# lpf.net
KiCad netlist of a schematic drawn in Altium Designer
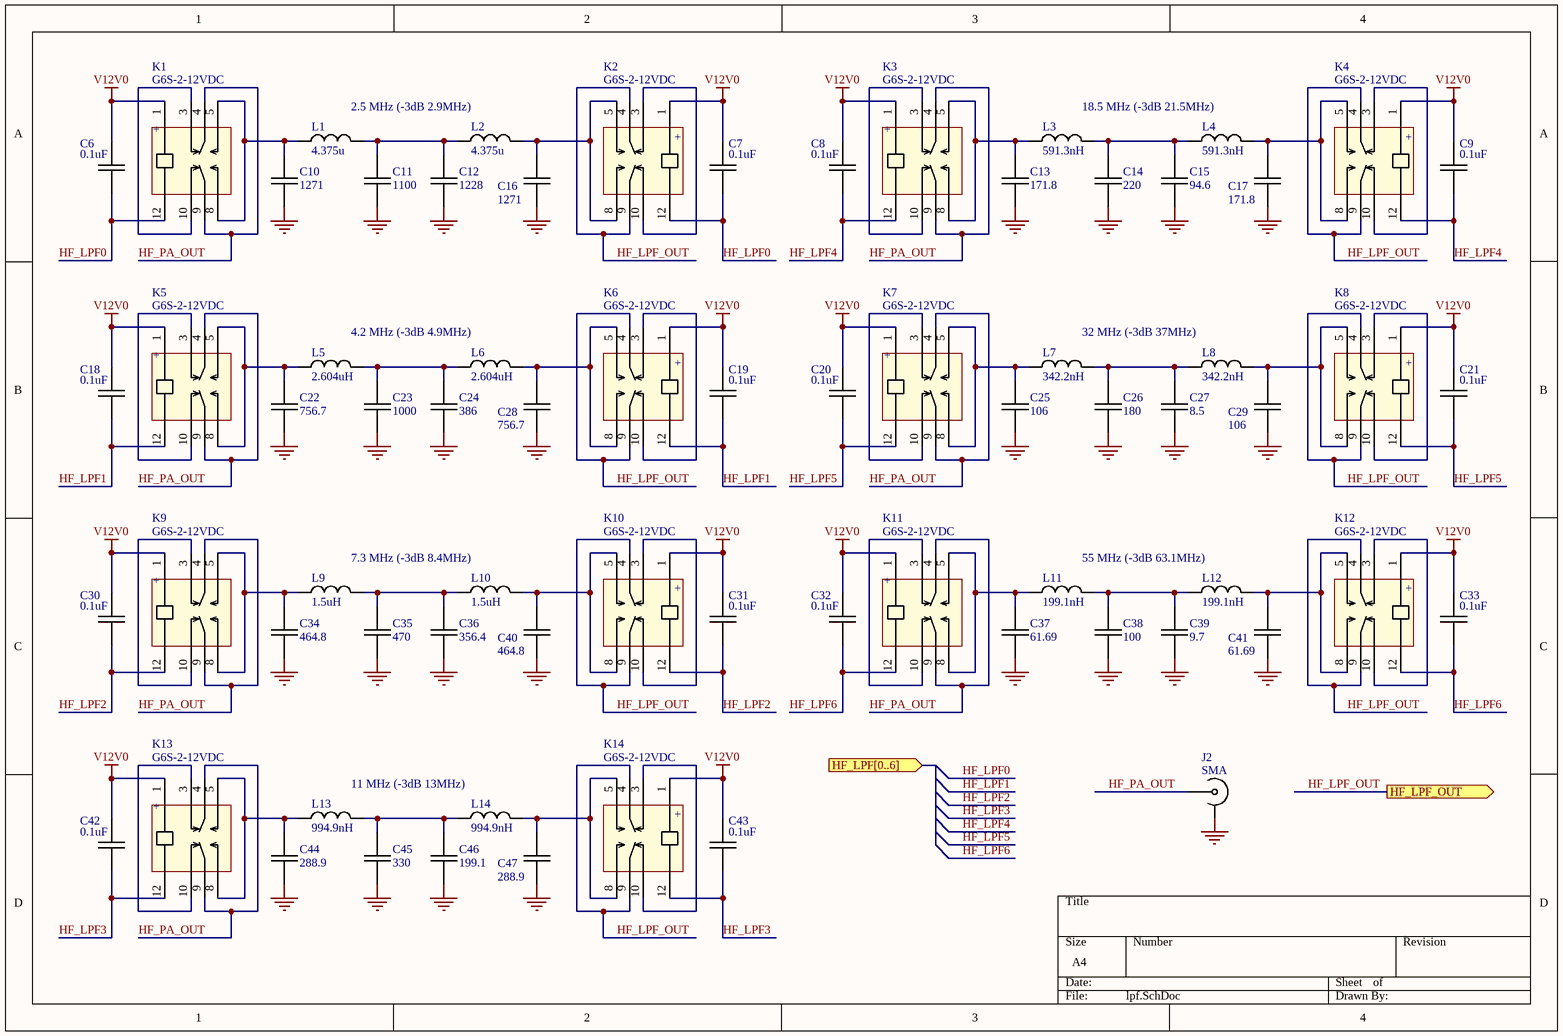
[diagram p0: lpf.SchDoc]

(export (version "E")
  (design (tool "Eeschema 10.0.6"))
  (components
    (comp (ref "C6")
      (value "0.1uF")
      (footprint "CAPC2013X100N")
      (description "Capacitor 2x1.25 mm")
      (libsource (lib "common-lib") (part "Cap0805"))
    )
    (comp (ref "C7")
      (value "0.1uF")
      (footprint "CAPC2013X100N")
      (description "Capacitor 2x1.25 mm")
      (libsource (lib "common-lib") (part "Cap0805"))
    )
    (comp (ref "C8")
      (value "0.1uF")
      (footprint "CAPC2013X100N")
      (description "Capacitor 2x1.25 mm")
      (libsource (lib "common-lib") (part "Cap0805"))
    )
    (comp (ref "C9")
      (value "0.1uF")
      (footprint "CAPC2013X100N")
      (description "Capacitor 2x1.25 mm")
      (libsource (lib "common-lib") (part "Cap0805"))
    )
    (comp (ref "C10")
      (value "1271")
      (footprint "CAPC3216X125N")
      (description "Capacitor 3.2x1.6 mm")
      (libsource (lib "common-lib") (part "Cap1206"))
    )
    (comp (ref "C11")
      (value "1100")
      (footprint "CAPC3216X125N")
      (description "Capacitor 3.2x1.6 mm")
      (libsource (lib "common-lib") (part "Cap1206"))
    )
    (comp (ref "C12")
      (value "1228")
      (footprint "CAPC3216X125N")
      (description "Capacitor 3.2x1.6 mm")
      (libsource (lib "common-lib") (part "Cap1206"))
    )
    (comp (ref "C13")
      (value "171.8")
      (footprint "CAPC3216X125N")
      (description "Capacitor 3.2x1.6 mm")
      (libsource (lib "common-lib") (part "Cap1206"))
    )
    (comp (ref "C14")
      (value "220")
      (footprint "CAPC3216X125N")
      (description "Capacitor 3.2x1.6 mm")
      (libsource (lib "common-lib") (part "Cap1206"))
    )
    (comp (ref "C15")
      (value "94.6")
      (footprint "CAPC3216X125N")
      (description "Capacitor 3.2x1.6 mm")
      (libsource (lib "common-lib") (part "Cap1206"))
    )
    (comp (ref "C16")
      (value "1271")
      (footprint "CAPC3216X125N")
      (description "Capacitor 3.2x1.6 mm")
      (libsource (lib "common-lib") (part "Cap1206"))
    )
    (comp (ref "C17")
      (value "171.8")
      (footprint "CAPC3216X125N")
      (description "Capacitor 3.2x1.6 mm")
      (libsource (lib "common-lib") (part "Cap1206"))
    )
    (comp (ref "C18")
      (value "0.1uF")
      (footprint "CAPC2013X100N")
      (description "Capacitor 2x1.25 mm")
      (libsource (lib "common-lib") (part "Cap0805"))
    )
    (comp (ref "C19")
      (value "0.1uF")
      (footprint "CAPC2013X100N")
      (description "Capacitor 2x1.25 mm")
      (libsource (lib "common-lib") (part "Cap0805"))
    )
    (comp (ref "C20")
      (value "0.1uF")
      (footprint "CAPC2013X100N")
      (description "Capacitor 2x1.25 mm")
      (libsource (lib "common-lib") (part "Cap0805"))
    )
    (comp (ref "C21")
      (value "0.1uF")
      (footprint "CAPC2013X100N")
      (description "Capacitor 2x1.25 mm")
      (libsource (lib "common-lib") (part "Cap0805"))
    )
    (comp (ref "C22")
      (value "756.7")
      (footprint "CAPC3216X125N")
      (description "Capacitor 3.2x1.6 mm")
      (libsource (lib "common-lib") (part "Cap1206"))
    )
    (comp (ref "C23")
      (value "1000")
      (footprint "CAPC3216X125N")
      (description "Capacitor 3.2x1.6 mm")
      (libsource (lib "common-lib") (part "Cap1206"))
    )
    (comp (ref "C24")
      (value "386")
      (footprint "CAPC3216X125N")
      (description "Capacitor 3.2x1.6 mm")
      (libsource (lib "common-lib") (part "Cap1206"))
    )
    (comp (ref "C25")
      (value "106")
      (footprint "CAPC3216X125N")
      (description "Capacitor 3.2x1.6 mm")
      (libsource (lib "common-lib") (part "Cap1206"))
    )
    (comp (ref "C26")
      (value "180")
      (footprint "CAPC3216X125N")
      (description "Capacitor 3.2x1.6 mm")
      (libsource (lib "common-lib") (part "Cap1206"))
    )
    (comp (ref "C27")
      (value "8.5")
      (footprint "CAPC3216X125N")
      (description "Capacitor 3.2x1.6 mm")
      (libsource (lib "common-lib") (part "Cap1206"))
    )
    (comp (ref "C28")
      (value "756.7")
      (footprint "CAPC3216X125N")
      (description "Capacitor 3.2x1.6 mm")
      (libsource (lib "common-lib") (part "Cap1206"))
    )
    (comp (ref "C29")
      (value "106")
      (footprint "CAPC3216X125N")
      (description "Capacitor 3.2x1.6 mm")
      (libsource (lib "common-lib") (part "Cap1206"))
    )
    (comp (ref "C30")
      (value "0.1uF")
      (footprint "CAPC2013X100N")
      (description "Capacitor 2x1.25 mm")
      (libsource (lib "common-lib") (part "Cap0805"))
    )
    (comp (ref "C31")
      (value "0.1uF")
      (footprint "CAPC2013X100N")
      (description "Capacitor 2x1.25 mm")
      (libsource (lib "common-lib") (part "Cap0805"))
    )
    (comp (ref "C32")
      (value "0.1uF")
      (footprint "CAPC2013X100N")
      (description "Capacitor 2x1.25 mm")
      (libsource (lib "common-lib") (part "Cap0805"))
    )
    (comp (ref "C33")
      (value "0.1uF")
      (footprint "CAPC2013X100N")
      (description "Capacitor 2x1.25 mm")
      (libsource (lib "common-lib") (part "Cap0805"))
    )
    (comp (ref "C34")
      (value "464.8")
      (footprint "CAPC3216X125N")
      (description "Capacitor 3.2x1.6 mm")
      (libsource (lib "common-lib") (part "Cap1206"))
    )
    (comp (ref "C35")
      (value "470")
      (footprint "CAPC3216X125N")
      (description "Capacitor 3.2x1.6 mm")
      (libsource (lib "common-lib") (part "Cap1206"))
    )
    (comp (ref "C36")
      (value "356.4")
      (footprint "CAPC3216X125N")
      (description "Capacitor 3.2x1.6 mm")
      (libsource (lib "common-lib") (part "Cap1206"))
    )
    (comp (ref "C37")
      (value "61.69")
      (footprint "CAPC3216X125N")
      (description "Capacitor 3.2x1.6 mm")
      (libsource (lib "common-lib") (part "Cap1206"))
    )
    (comp (ref "C38")
      (value "100")
      (footprint "CAPC3216X125N")
      (description "Capacitor 3.2x1.6 mm")
      (libsource (lib "common-lib") (part "Cap1206"))
    )
    (comp (ref "C39")
      (value "9.7")
      (footprint "CAPC3216X125N")
      (description "Capacitor 3.2x1.6 mm")
      (libsource (lib "common-lib") (part "Cap1206"))
    )
    (comp (ref "C40")
      (value "464.8")
      (footprint "CAPC3216X125N")
      (description "Capacitor 3.2x1.6 mm")
      (libsource (lib "common-lib") (part "Cap1206"))
    )
    (comp (ref "C41")
      (value "61.69")
      (footprint "CAPC3216X125N")
      (description "Capacitor 3.2x1.6 mm")
      (libsource (lib "common-lib") (part "Cap1206"))
    )
    (comp (ref "C42")
      (value "0.1uF")
      (footprint "CAPC2013X100N")
      (description "Capacitor 2x1.25 mm")
      (libsource (lib "common-lib") (part "Cap0805"))
    )
    (comp (ref "C43")
      (value "0.1uF")
      (footprint "CAPC2013X100N")
      (description "Capacitor 2x1.25 mm")
      (libsource (lib "common-lib") (part "Cap0805"))
    )
    (comp (ref "C44")
      (value "288.9")
      (footprint "CAPC3216X125N")
      (description "Capacitor 3.2x1.6 mm")
      (libsource (lib "common-lib") (part "Cap1206"))
    )
    (comp (ref "C45")
      (value "330")
      (footprint "CAPC3216X125N")
      (description "Capacitor 3.2x1.6 mm")
      (libsource (lib "common-lib") (part "Cap1206"))
    )
    (comp (ref "C46")
      (value "199.1")
      (footprint "CAPC3216X125N")
      (description "Capacitor 3.2x1.6 mm")
      (libsource (lib "common-lib") (part "Cap1206"))
    )
    (comp (ref "C47")
      (value "288.9")
      (footprint "CAPC3216X125N")
      (description "Capacitor 3.2x1.6 mm")
      (libsource (lib "common-lib") (part "Cap1206"))
    )
    (comp (ref "J2") (value "SMA") (footprint "SMA002") (libsource (lib "PALib") (part "RF Connector")))
    (comp (ref "K1")
      (value "G6S-2-12VDC")
      (footprint "G6S-2")
      (description "Compact, Industry-Standard 2-pole relay")
      (libsource (lib "PALib") (part "G6S-2-12VDC"))
    )
    (comp (ref "K2")
      (value "G6S-2-12VDC")
      (footprint "G6S-2")
      (description "Compact, Industry-Standard 2-pole relay")
      (libsource (lib "") (part "G6S-2-12VDC_1"))
    )
    (comp (ref "K3")
      (value "G6S-2-12VDC")
      (footprint "G6S-2")
      (description "Compact, Industry-Standard 2-pole relay")
      (libsource (lib "PALib") (part "G6S-2-12VDC"))
    )
    (comp (ref "K4")
      (value "G6S-2-12VDC")
      (footprint "G6S-2")
      (description "Compact, Industry-Standard 2-pole relay")
      (libsource (lib "") (part "G6S-2-12VDC_1"))
    )
    (comp (ref "K5")
      (value "G6S-2-12VDC")
      (footprint "G6S-2")
      (description "Compact, Industry-Standard 2-pole relay")
      (libsource (lib "PALib") (part "G6S-2-12VDC"))
    )
    (comp (ref "K6")
      (value "G6S-2-12VDC")
      (footprint "G6S-2")
      (description "Compact, Industry-Standard 2-pole relay")
      (libsource (lib "") (part "G6S-2-12VDC_1"))
    )
    (comp (ref "K7")
      (value "G6S-2-12VDC")
      (footprint "G6S-2")
      (description "Compact, Industry-Standard 2-pole relay")
      (libsource (lib "PALib") (part "G6S-2-12VDC"))
    )
    (comp (ref "K8")
      (value "G6S-2-12VDC")
      (footprint "G6S-2")
      (description "Compact, Industry-Standard 2-pole relay")
      (libsource (lib "") (part "G6S-2-12VDC_1"))
    )
    (comp (ref "K9")
      (value "G6S-2-12VDC")
      (footprint "G6S-2")
      (description "Compact, Industry-Standard 2-pole relay")
      (libsource (lib "PALib") (part "G6S-2-12VDC"))
    )
    (comp (ref "K10")
      (value "G6S-2-12VDC")
      (footprint "G6S-2")
      (description "Compact, Industry-Standard 2-pole relay")
      (libsource (lib "") (part "G6S-2-12VDC_1"))
    )
    (comp (ref "K11")
      (value "G6S-2-12VDC")
      (footprint "G6S-2")
      (description "Compact, Industry-Standard 2-pole relay")
      (libsource (lib "PALib") (part "G6S-2-12VDC"))
    )
    (comp (ref "K12")
      (value "G6S-2-12VDC")
      (footprint "G6S-2")
      (description "Compact, Industry-Standard 2-pole relay")
      (libsource (lib "") (part "G6S-2-12VDC_1"))
    )
    (comp (ref "K13")
      (value "G6S-2-12VDC")
      (footprint "G6S-2")
      (description "Compact, Industry-Standard 2-pole relay")
      (libsource (lib "PALib") (part "G6S-2-12VDC"))
    )
    (comp (ref "K14")
      (value "G6S-2-12VDC")
      (footprint "G6S-2")
      (description "Compact, Industry-Standard 2-pole relay")
      (libsource (lib "") (part "G6S-2-12VDC_1"))
    )
    (comp (ref "L1")
      (value "4.375u")
      (footprint "T50-2")
      (description "T50-2")
      (libsource (lib "") (part "Inductor_1"))
    )
    (comp (ref "L2")
      (value "4.375u")
      (footprint "T50-2")
      (description "T50-2")
      (libsource (lib "PALib") (part "Inductor"))
    )
    (comp (ref "L3")
      (value "591.3nH")
      (footprint "T50-6")
      (description "T50-6")
      (libsource (lib "PALib") (part "Inductor"))
    )
    (comp (ref "L4")
      (value "591.3nH")
      (footprint "T50-6")
      (description "T50-6")
      (libsource (lib "PALib") (part "Inductor"))
    )
    (comp (ref "L5")
      (value "2.604uH")
      (footprint "T50-2")
      (description "T50-2")
      (libsource (lib "") (part "Inductor_1"))
    )
    (comp (ref "L6")
      (value "2.604uH")
      (footprint "T50-2")
      (description "T50-2")
      (libsource (lib "PALib") (part "Inductor"))
    )
    (comp (ref "L7")
      (value "342.2nH")
      (footprint "T50-6")
      (description "T50-6")
      (libsource (lib "PALib") (part "Inductor"))
    )
    (comp (ref "L8")
      (value "342.2nH")
      (footprint "T50-6")
      (description "T50-6")
      (libsource (lib "PALib") (part "Inductor"))
    )
    (comp (ref "L9")
      (value "1.5uH")
      (footprint "T50-6")
      (description "T50-6")
      (libsource (lib "") (part "Inductor_1"))
    )
    (comp (ref "L10")
      (value "1.5uH")
      (footprint "T50-6")
      (description "T50-6")
      (libsource (lib "PALib") (part "Inductor"))
    )
    (comp (ref "L11")
      (value "199.1nH")
      (footprint "T50-6")
      (description "T50-6")
      (libsource (lib "PALib") (part "Inductor"))
    )
    (comp (ref "L12")
      (value "199.1nH")
      (footprint "T50-6")
      (description "T50-6")
      (libsource (lib "PALib") (part "Inductor"))
    )
    (comp (ref "L13")
      (value "994.9nH")
      (footprint "T50-6")
      (description "T50-6")
      (libsource (lib "") (part "Inductor_1"))
    )
    (comp (ref "L14")
      (value "994.9nH")
      (footprint "T50-6")
      (description "T50-6")
      (libsource (lib "PALib") (part "Inductor"))
    )
  )
  (nets
    (net (code "1") (name "/HF_LPF0") (class "Default")
      (node (ref "C6") (pin "1") (pintype "passive"))
      (node (ref "C7") (pin "1") (pintype "passive"))
      (node (ref "K1") (pin "12") (pintype "passive"))
      (node (ref "K2") (pin "12") (pintype "passive"))
    )
    (net (code "2") (name "/HF_LPF1") (class "Default")
      (node (ref "C18") (pin "1") (pintype "passive"))
      (node (ref "C19") (pin "1") (pintype "passive"))
      (node (ref "K5") (pin "12") (pintype "passive"))
      (node (ref "K6") (pin "12") (pintype "passive"))
    )
    (net (code "3") (name "/HF_LPF2") (class "Default")
      (node (ref "C30") (pin "1") (pintype "passive"))
      (node (ref "C31") (pin "1") (pintype "passive"))
      (node (ref "K10") (pin "12") (pintype "passive"))
      (node (ref "K9") (pin "12") (pintype "passive"))
    )
    (net (code "4") (name "/HF_LPF3") (class "Default")
      (node (ref "C42") (pin "1") (pintype "passive"))
      (node (ref "C43") (pin "1") (pintype "passive"))
      (node (ref "K13") (pin "12") (pintype "passive"))
      (node (ref "K14") (pin "12") (pintype "passive"))
    )
    (net (code "5") (name "/HF_LPF4") (class "Default")
      (node (ref "C8") (pin "1") (pintype "passive"))
      (node (ref "C9") (pin "1") (pintype "passive"))
      (node (ref "K3") (pin "12") (pintype "passive"))
      (node (ref "K4") (pin "12") (pintype "passive"))
    )
    (net (code "6") (name "/HF_LPF5") (class "Default")
      (node (ref "C20") (pin "1") (pintype "passive"))
      (node (ref "C21") (pin "1") (pintype "passive"))
      (node (ref "K7") (pin "12") (pintype "passive"))
      (node (ref "K8") (pin "12") (pintype "passive"))
    )
    (net (code "7") (name "/HF_LPF6") (class "Default")
      (node (ref "C32") (pin "1") (pintype "passive"))
      (node (ref "C33") (pin "1") (pintype "passive"))
      (node (ref "K11") (pin "12") (pintype "passive"))
      (node (ref "K12") (pin "12") (pintype "passive"))
    )
    (net (code "9") (name "/HF_LPF_OUT") (class "Default")
      (node (ref "K10") (pin "4") (pintype "passive"))
      (node (ref "K10") (pin "9") (pintype "passive"))
      (node (ref "K12") (pin "4") (pintype "passive"))
      (node (ref "K12") (pin "9") (pintype "passive"))
      (node (ref "K14") (pin "4") (pintype "passive"))
      (node (ref "K14") (pin "9") (pintype "passive"))
      (node (ref "K2") (pin "4") (pintype "passive"))
      (node (ref "K2") (pin "9") (pintype "passive"))
      (node (ref "K4") (pin "4") (pintype "passive"))
      (node (ref "K4") (pin "9") (pintype "passive"))
      (node (ref "K6") (pin "4") (pintype "passive"))
      (node (ref "K6") (pin "9") (pintype "passive"))
      (node (ref "K8") (pin "4") (pintype "passive"))
      (node (ref "K8") (pin "9") (pintype "passive"))
    )
    (net (code "10") (name "/HF_PA_OUT") (class "Default")
      (node (ref "J2") (pin "1") (pinfunction "RF_1") (pintype "passive"))
      (node (ref "K1") (pin "4") (pintype "passive"))
      (node (ref "K1") (pin "9") (pintype "passive"))
      (node (ref "K11") (pin "4") (pintype "passive"))
      (node (ref "K11") (pin "9") (pintype "passive"))
      (node (ref "K13") (pin "4") (pintype "passive"))
      (node (ref "K13") (pin "9") (pintype "passive"))
      (node (ref "K3") (pin "4") (pintype "passive"))
      (node (ref "K3") (pin "9") (pintype "passive"))
      (node (ref "K5") (pin "4") (pintype "passive"))
      (node (ref "K5") (pin "9") (pintype "passive"))
      (node (ref "K7") (pin "4") (pintype "passive"))
      (node (ref "K7") (pin "9") (pintype "passive"))
      (node (ref "K9") (pin "4") (pintype "passive"))
      (node (ref "K9") (pin "9") (pintype "passive"))
    )
    (net (code "11") (name "GND") (class "Default")
      (node (ref "C10") (pin "1") (pintype "passive"))
      (node (ref "C11") (pin "1") (pintype "passive"))
      (node (ref "C12") (pin "1") (pintype "passive"))
      (node (ref "C13") (pin "1") (pintype "passive"))
      (node (ref "C14") (pin "1") (pintype "passive"))
      (node (ref "C15") (pin "1") (pintype "passive"))
      (node (ref "C16") (pin "1") (pintype "passive"))
      (node (ref "C17") (pin "1") (pintype "passive"))
      (node (ref "C22") (pin "1") (pintype "passive"))
      (node (ref "C23") (pin "1") (pintype "passive"))
      (node (ref "C24") (pin "1") (pintype "passive"))
      (node (ref "C25") (pin "1") (pintype "passive"))
      (node (ref "C26") (pin "1") (pintype "passive"))
      (node (ref "C27") (pin "1") (pintype "passive"))
      (node (ref "C28") (pin "1") (pintype "passive"))
      (node (ref "C29") (pin "1") (pintype "passive"))
      (node (ref "C34") (pin "1") (pintype "passive"))
      (node (ref "C35") (pin "1") (pintype "passive"))
      (node (ref "C36") (pin "1") (pintype "passive"))
      (node (ref "C37") (pin "1") (pintype "passive"))
      (node (ref "C38") (pin "1") (pintype "passive"))
      (node (ref "C39") (pin "1") (pintype "passive"))
      (node (ref "C40") (pin "1") (pintype "passive"))
      (node (ref "C41") (pin "1") (pintype "passive"))
      (node (ref "C44") (pin "1") (pintype "passive"))
      (node (ref "C45") (pin "1") (pintype "passive"))
      (node (ref "C46") (pin "1") (pintype "passive"))
      (node (ref "C47") (pin "1") (pintype "passive"))
      (node (ref "J2") (pin "2") (pinfunction "GND_2") (pintype "passive"))
    )
    (net (code "12") (name "Net-(C10-Pad2)") (class "Default")
      (node (ref "C10") (pin "2") (pintype "passive"))
      (node (ref "K1") (pin "5") (pintype "passive"))
      (node (ref "K1") (pin "8") (pintype "passive"))
      (node (ref "L1") (pin "1") (pintype "passive"))
    )
    (net (code "13") (name "Net-(C11-Pad2)") (class "Default")
      (node (ref "C11") (pin "2") (pintype "passive"))
      (node (ref "C12") (pin "2") (pintype "passive"))
      (node (ref "L1") (pin "2") (pintype "passive"))
      (node (ref "L2") (pin "1") (pintype "passive"))
    )
    (net (code "14") (name "Net-(C13-Pad2)") (class "Default")
      (node (ref "C13") (pin "2") (pintype "passive"))
      (node (ref "K3") (pin "5") (pintype "passive"))
      (node (ref "K3") (pin "8") (pintype "passive"))
      (node (ref "L3") (pin "1") (pintype "passive"))
    )
    (net (code "15") (name "Net-(C14-Pad2)") (class "Default")
      (node (ref "C14") (pin "2") (pintype "passive"))
      (node (ref "C15") (pin "2") (pintype "passive"))
      (node (ref "L3") (pin "2") (pintype "passive"))
      (node (ref "L4") (pin "1") (pintype "passive"))
    )
    (net (code "16") (name "Net-(C16-Pad2)") (class "Default")
      (node (ref "C16") (pin "2") (pintype "passive"))
      (node (ref "K2") (pin "5") (pintype "passive"))
      (node (ref "K2") (pin "8") (pintype "passive"))
      (node (ref "L2") (pin "2") (pintype "passive"))
    )
    (net (code "17") (name "Net-(C17-Pad2)") (class "Default")
      (node (ref "C17") (pin "2") (pintype "passive"))
      (node (ref "K4") (pin "5") (pintype "passive"))
      (node (ref "K4") (pin "8") (pintype "passive"))
      (node (ref "L4") (pin "2") (pintype "passive"))
    )
    (net (code "18") (name "Net-(C22-Pad2)") (class "Default")
      (node (ref "C22") (pin "2") (pintype "passive"))
      (node (ref "K5") (pin "5") (pintype "passive"))
      (node (ref "K5") (pin "8") (pintype "passive"))
      (node (ref "L5") (pin "1") (pintype "passive"))
    )
    (net (code "19") (name "Net-(C23-Pad2)") (class "Default")
      (node (ref "C23") (pin "2") (pintype "passive"))
      (node (ref "C24") (pin "2") (pintype "passive"))
      (node (ref "L5") (pin "2") (pintype "passive"))
      (node (ref "L6") (pin "1") (pintype "passive"))
    )
    (net (code "20") (name "Net-(C25-Pad2)") (class "Default")
      (node (ref "C25") (pin "2") (pintype "passive"))
      (node (ref "K7") (pin "5") (pintype "passive"))
      (node (ref "K7") (pin "8") (pintype "passive"))
      (node (ref "L7") (pin "1") (pintype "passive"))
    )
    (net (code "21") (name "Net-(C26-Pad2)") (class "Default")
      (node (ref "C26") (pin "2") (pintype "passive"))
      (node (ref "C27") (pin "2") (pintype "passive"))
      (node (ref "L7") (pin "2") (pintype "passive"))
      (node (ref "L8") (pin "1") (pintype "passive"))
    )
    (net (code "22") (name "Net-(C28-Pad2)") (class "Default")
      (node (ref "C28") (pin "2") (pintype "passive"))
      (node (ref "K6") (pin "5") (pintype "passive"))
      (node (ref "K6") (pin "8") (pintype "passive"))
      (node (ref "L6") (pin "2") (pintype "passive"))
    )
    (net (code "23") (name "Net-(C29-Pad2)") (class "Default")
      (node (ref "C29") (pin "2") (pintype "passive"))
      (node (ref "K8") (pin "5") (pintype "passive"))
      (node (ref "K8") (pin "8") (pintype "passive"))
      (node (ref "L8") (pin "2") (pintype "passive"))
    )
    (net (code "24") (name "Net-(C34-Pad2)") (class "Default")
      (node (ref "C34") (pin "2") (pintype "passive"))
      (node (ref "K9") (pin "5") (pintype "passive"))
      (node (ref "K9") (pin "8") (pintype "passive"))
      (node (ref "L9") (pin "1") (pintype "passive"))
    )
    (net (code "25") (name "Net-(C35-Pad2)") (class "Default")
      (node (ref "C35") (pin "2") (pintype "passive"))
      (node (ref "C36") (pin "2") (pintype "passive"))
      (node (ref "L10") (pin "1") (pintype "passive"))
      (node (ref "L9") (pin "2") (pintype "passive"))
    )
    (net (code "26") (name "Net-(C37-Pad2)") (class "Default")
      (node (ref "C37") (pin "2") (pintype "passive"))
      (node (ref "K11") (pin "5") (pintype "passive"))
      (node (ref "K11") (pin "8") (pintype "passive"))
      (node (ref "L11") (pin "1") (pintype "passive"))
    )
    (net (code "27") (name "Net-(C38-Pad2)") (class "Default")
      (node (ref "C38") (pin "2") (pintype "passive"))
      (node (ref "C39") (pin "2") (pintype "passive"))
      (node (ref "L11") (pin "2") (pintype "passive"))
      (node (ref "L12") (pin "1") (pintype "passive"))
    )
    (net (code "28") (name "Net-(C40-Pad2)") (class "Default")
      (node (ref "C40") (pin "2") (pintype "passive"))
      (node (ref "K10") (pin "5") (pintype "passive"))
      (node (ref "K10") (pin "8") (pintype "passive"))
      (node (ref "L10") (pin "2") (pintype "passive"))
    )
    (net (code "29") (name "Net-(C41-Pad2)") (class "Default")
      (node (ref "C41") (pin "2") (pintype "passive"))
      (node (ref "K12") (pin "5") (pintype "passive"))
      (node (ref "K12") (pin "8") (pintype "passive"))
      (node (ref "L12") (pin "2") (pintype "passive"))
    )
    (net (code "30") (name "Net-(C44-Pad2)") (class "Default")
      (node (ref "C44") (pin "2") (pintype "passive"))
      (node (ref "K13") (pin "5") (pintype "passive"))
      (node (ref "K13") (pin "8") (pintype "passive"))
      (node (ref "L13") (pin "1") (pintype "passive"))
    )
    (net (code "31") (name "Net-(C45-Pad2)") (class "Default")
      (node (ref "C45") (pin "2") (pintype "passive"))
      (node (ref "C46") (pin "2") (pintype "passive"))
      (node (ref "L13") (pin "2") (pintype "passive"))
      (node (ref "L14") (pin "1") (pintype "passive"))
    )
    (net (code "32") (name "Net-(C47-Pad2)") (class "Default")
      (node (ref "C47") (pin "2") (pintype "passive"))
      (node (ref "K14") (pin "5") (pintype "passive"))
      (node (ref "K14") (pin "8") (pintype "passive"))
      (node (ref "L14") (pin "2") (pintype "passive"))
    )
    (net (code "33") (name "Net-(K1-Pad10)") (class "Default")
      (node (ref "K1") (pin "10") (pintype "passive"))
      (node (ref "K1") (pin "3") (pintype "passive"))
    )
    (net (code "34") (name "Net-(K2-Pad10)") (class "Default")
      (node (ref "K2") (pin "10") (pintype "passive"))
      (node (ref "K2") (pin "3") (pintype "passive"))
    )
    (net (code "35") (name "Net-(K3-Pad10)") (class "Default")
      (node (ref "K3") (pin "10") (pintype "passive"))
      (node (ref "K3") (pin "3") (pintype "passive"))
    )
    (net (code "36") (name "Net-(K4-Pad10)") (class "Default")
      (node (ref "K4") (pin "10") (pintype "passive"))
      (node (ref "K4") (pin "3") (pintype "passive"))
    )
    (net (code "37") (name "Net-(K5-Pad10)") (class "Default")
      (node (ref "K5") (pin "10") (pintype "passive"))
      (node (ref "K5") (pin "3") (pintype "passive"))
    )
    (net (code "38") (name "Net-(K6-Pad10)") (class "Default")
      (node (ref "K6") (pin "10") (pintype "passive"))
      (node (ref "K6") (pin "3") (pintype "passive"))
    )
    (net (code "39") (name "Net-(K7-Pad10)") (class "Default")
      (node (ref "K7") (pin "10") (pintype "passive"))
      (node (ref "K7") (pin "3") (pintype "passive"))
    )
    (net (code "40") (name "Net-(K8-Pad10)") (class "Default")
      (node (ref "K8") (pin "10") (pintype "passive"))
      (node (ref "K8") (pin "3") (pintype "passive"))
    )
    (net (code "41") (name "Net-(K9-Pad10)") (class "Default")
      (node (ref "K9") (pin "10") (pintype "passive"))
      (node (ref "K9") (pin "3") (pintype "passive"))
    )
    (net (code "42") (name "Net-(K10-Pad10)") (class "Default")
      (node (ref "K10") (pin "10") (pintype "passive"))
      (node (ref "K10") (pin "3") (pintype "passive"))
    )
    (net (code "43") (name "Net-(K11-Pad10)") (class "Default")
      (node (ref "K11") (pin "10") (pintype "passive"))
      (node (ref "K11") (pin "3") (pintype "passive"))
    )
    (net (code "44") (name "Net-(K12-Pad10)") (class "Default")
      (node (ref "K12") (pin "10") (pintype "passive"))
      (node (ref "K12") (pin "3") (pintype "passive"))
    )
    (net (code "45") (name "Net-(K13-Pad10)") (class "Default")
      (node (ref "K13") (pin "10") (pintype "passive"))
      (node (ref "K13") (pin "3") (pintype "passive"))
    )
    (net (code "46") (name "Net-(K14-Pad10)") (class "Default")
      (node (ref "K14") (pin "10") (pintype "passive"))
      (node (ref "K14") (pin "3") (pintype "passive"))
    )
    (net (code "47") (name "V12V0") (class "Default")
      (node (ref "C18") (pin "2") (pintype "passive"))
      (node (ref "C19") (pin "2") (pintype "passive"))
      (node (ref "C20") (pin "2") (pintype "passive"))
      (node (ref "C21") (pin "2") (pintype "passive"))
      (node (ref "C30") (pin "2") (pintype "passive"))
      (node (ref "C31") (pin "2") (pintype "passive"))
      (node (ref "C32") (pin "2") (pintype "passive"))
      (node (ref "C33") (pin "2") (pintype "passive"))
      (node (ref "C42") (pin "2") (pintype "passive"))
      (node (ref "C43") (pin "2") (pintype "passive"))
      (node (ref "C6") (pin "2") (pintype "passive"))
      (node (ref "C7") (pin "2") (pintype "passive"))
      (node (ref "C8") (pin "2") (pintype "passive"))
      (node (ref "C9") (pin "2") (pintype "passive"))
      (node (ref "K1") (pin "1") (pintype "passive"))
      (node (ref "K10") (pin "1") (pintype "passive"))
      (node (ref "K11") (pin "1") (pintype "passive"))
      (node (ref "K12") (pin "1") (pintype "passive"))
      (node (ref "K13") (pin "1") (pintype "passive"))
      (node (ref "K14") (pin "1") (pintype "passive"))
      (node (ref "K2") (pin "1") (pintype "passive"))
      (node (ref "K3") (pin "1") (pintype "passive"))
      (node (ref "K4") (pin "1") (pintype "passive"))
      (node (ref "K5") (pin "1") (pintype "passive"))
      (node (ref "K6") (pin "1") (pintype "passive"))
      (node (ref "K7") (pin "1") (pintype "passive"))
      (node (ref "K8") (pin "1") (pintype "passive"))
      (node (ref "K9") (pin "1") (pintype "passive"))
    )
  )
)
